# BT_HC05_v1.net
KiCad netlist of a schematic drawn in EAGLE
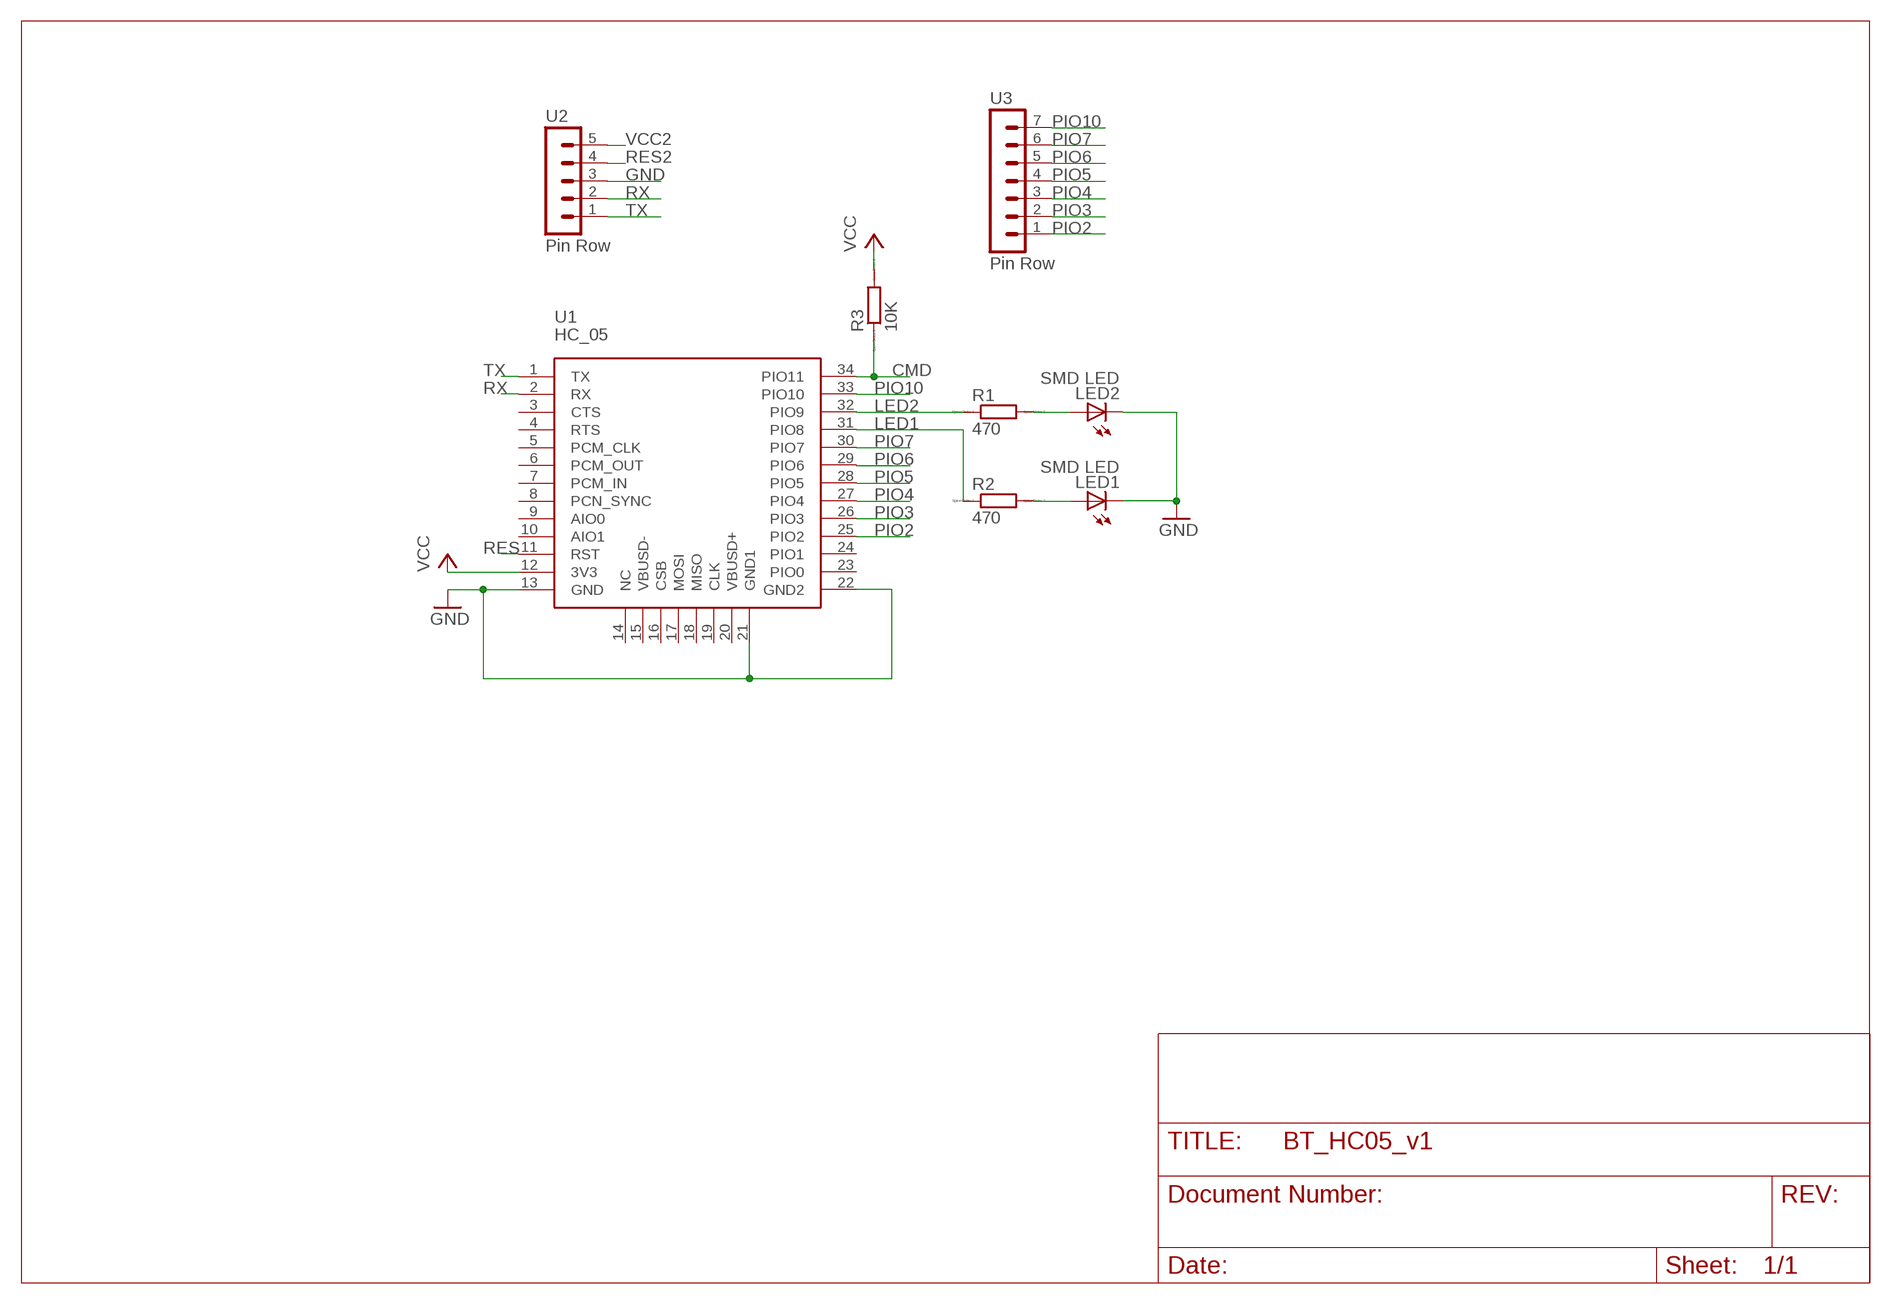
[diagram p0: schematic, sheet 1]

(export (version "E")
  (design (tool "Eeschema 10.0.6"))
  (components
    (comp (ref "LED1")
      (value "SMD LED")
      (footprint "eagle-import:CHIP-LED0805")
      (libsource (lib "eagle-import") (part "LEDCHIP-LED0805"))
    )
    (comp (ref "LED2")
      (value "SMD LED")
      (footprint "eagle-import:CHIP-LED0805")
      (libsource (lib "eagle-import") (part "LEDCHIP-LED0805"))
    )
    (comp (ref "R1")
      (value "470")
      (footprint "eagle-import:R0805")
      (libsource (lib "eagle-import") (part "R"))
    )
    (comp (ref "R2")
      (value "470")
      (footprint "eagle-import:R0805")
      (libsource (lib "eagle-import") (part "R"))
    )
    (comp (ref "R3")
      (value "10K")
      (footprint "eagle-import:R0805")
      (libsource (lib "eagle-import") (part "R"))
    )
    (comp (ref "U1")
      (value "HC_05")
      (footprint "eagle-import:BLUETOOTH_SMD")
      (libsource (lib "eagle-import") (part "HC_05"))
    )
    (comp (ref "U2")
      (value "Pin Row")
      (footprint "eagle-import:MAR05-1")
      (libsource (lib "eagle-import") (part "MAR05-1"))
    )
    (comp (ref "U3")
      (value "Pin Row")
      (footprint "eagle-import:MA07-1")
      (libsource (lib "eagle-import") (part "MA07-1"))
    )
  )
  (nets
    (net (code "1") (name "/CMD") (class "Default")
      (node (ref "R3") (pin "1") (pinfunction "1_1") (pintype "passive"))
      (node (ref "U1") (pin "34") (pinfunction "PIO11_34") (pintype "bidirectional"))
    )
    (net (code "2") (name "/LED1") (class "Default")
      (node (ref "R2") (pin "1") (pinfunction "1_1") (pintype "passive"))
      (node (ref "U1") (pin "31") (pinfunction "PIO8_31") (pintype "bidirectional"))
    )
    (net (code "3") (name "/LED2") (class "Default")
      (node (ref "R1") (pin "1") (pinfunction "1_1") (pintype "passive"))
      (node (ref "U1") (pin "32") (pinfunction "PIO9_32") (pintype "bidirectional"))
    )
    (net (code "4") (name "/PIO2") (class "Default")
      (node (ref "U1") (pin "25") (pinfunction "PIO2_25") (pintype "bidirectional"))
      (node (ref "U3") (pin "1") (pinfunction "1_1") (pintype "passive"))
    )
    (net (code "5") (name "/PIO3") (class "Default")
      (node (ref "U1") (pin "26") (pinfunction "PIO3_26") (pintype "bidirectional"))
      (node (ref "U3") (pin "2") (pinfunction "2_2") (pintype "passive"))
    )
    (net (code "6") (name "/PIO4") (class "Default")
      (node (ref "U1") (pin "27") (pinfunction "PIO4_27") (pintype "bidirectional"))
      (node (ref "U3") (pin "3") (pinfunction "3_3") (pintype "passive"))
    )
    (net (code "7") (name "/PIO5") (class "Default")
      (node (ref "U1") (pin "28") (pinfunction "PIO5_28") (pintype "bidirectional"))
      (node (ref "U3") (pin "4") (pinfunction "4_4") (pintype "passive"))
    )
    (net (code "8") (name "/PIO6") (class "Default")
      (node (ref "U1") (pin "29") (pinfunction "PIO6_29") (pintype "bidirectional"))
      (node (ref "U3") (pin "5") (pinfunction "5_5") (pintype "passive"))
    )
    (net (code "9") (name "/PIO7") (class "Default")
      (node (ref "U1") (pin "30") (pinfunction "PIO7_30") (pintype "bidirectional"))
      (node (ref "U3") (pin "6") (pinfunction "6_6") (pintype "passive"))
    )
    (net (code "10") (name "/PIO10") (class "Default")
      (node (ref "U1") (pin "33") (pinfunction "PIO10_33") (pintype "bidirectional"))
      (node (ref "U3") (pin "7") (pinfunction "7_7") (pintype "passive"))
    )
    (net (code "11") (name "/RES") (class "Default")
      (node (ref "U1") (pin "11") (pinfunction "RST_11") (pintype "bidirectional"))
    )
    (net (code "12") (name "/RES2") (class "Default")
      (node (ref "U2") (pin "4") (pinfunction "4_4") (pintype "passive"))
    )
    (net (code "13") (name "/RX") (class "Default")
      (node (ref "U1") (pin "2") (pinfunction "RX_2") (pintype "bidirectional"))
      (node (ref "U2") (pin "2") (pinfunction "2_2") (pintype "passive"))
    )
    (net (code "14") (name "/TX") (class "Default")
      (node (ref "U1") (pin "1") (pinfunction "TX_1") (pintype "bidirectional"))
      (node (ref "U2") (pin "1") (pinfunction "1_1") (pintype "passive"))
    )
    (net (code "15") (name "/VCC2") (class "Default")
      (node (ref "U2") (pin "5") (pinfunction "5_5") (pintype "passive"))
    )
    (net (code "16") (name "GND") (class "Default")
      (node (ref "LED1") (pin "C") (pinfunction "C_C") (pintype "passive"))
      (node (ref "LED2") (pin "C") (pinfunction "C_C") (pintype "passive"))
      (node (ref "U1") (pin "13") (pinfunction "GND_13") (pintype "bidirectional"))
      (node (ref "U1") (pin "21") (pinfunction "GND1_21") (pintype "bidirectional"))
      (node (ref "U1") (pin "22") (pinfunction "GND2_22") (pintype "bidirectional"))
      (node (ref "U2") (pin "3") (pinfunction "3_3") (pintype "passive"))
    )
    (net (code "17") (name "Net-(LED1-PadA)") (class "Default")
      (node (ref "LED1") (pin "A") (pinfunction "A_A") (pintype "passive"))
      (node (ref "R2") (pin "2") (pinfunction "2_2") (pintype "passive"))
    )
    (net (code "18") (name "Net-(LED2-PadA)") (class "Default")
      (node (ref "LED2") (pin "A") (pinfunction "A_A") (pintype "passive"))
      (node (ref "R1") (pin "2") (pinfunction "2_2") (pintype "passive"))
    )
    (net (code "19") (name "VCC") (class "Default")
      (node (ref "R3") (pin "2") (pinfunction "2_2") (pintype "passive"))
      (node (ref "U1") (pin "12") (pinfunction "3V3_12") (pintype "bidirectional"))
    )
    (net (code "20") (name "unconnected-(U1-AIO0-Pad9)") (class "Default")
      (node (ref "U1") (pin "9") (pinfunction "AIO0_9") (pintype "bidirectional"))
    )
    (net (code "21") (name "unconnected-(U1-AIO1-Pad10)") (class "Default")
      (node (ref "U1") (pin "10") (pinfunction "AIO1_10") (pintype "bidirectional"))
    )
    (net (code "22") (name "unconnected-(U1-CLK-Pad19)") (class "Default")
      (node (ref "U1") (pin "19") (pinfunction "CLK_19") (pintype "bidirectional"))
    )
    (net (code "23") (name "unconnected-(U1-CSB-Pad16)") (class "Default")
      (node (ref "U1") (pin "16") (pinfunction "CSB_16") (pintype "bidirectional"))
    )
    (net (code "24") (name "unconnected-(U1-CTS-Pad3)") (class "Default")
      (node (ref "U1") (pin "3") (pinfunction "CTS_3") (pintype "bidirectional"))
    )
    (net (code "25") (name "unconnected-(U1-MISO-Pad18)") (class "Default")
      (node (ref "U1") (pin "18") (pinfunction "MISO_18") (pintype "bidirectional"))
    )
    (net (code "26") (name "unconnected-(U1-MOSI-Pad17)") (class "Default")
      (node (ref "U1") (pin "17") (pinfunction "MOSI_17") (pintype "bidirectional"))
    )
    (net (code "27") (name "unconnected-(U1-NC-Pad14)") (class "Default")
      (node (ref "U1") (pin "14") (pinfunction "NC_14") (pintype "bidirectional"))
    )
    (net (code "28") (name "unconnected-(U1-PCM_CLK-Pad5)") (class "Default")
      (node (ref "U1") (pin "5") (pinfunction "PCM_CLK_5") (pintype "bidirectional"))
    )
    (net (code "29") (name "unconnected-(U1-PCM_IN-Pad7)") (class "Default")
      (node (ref "U1") (pin "7") (pinfunction "PCM_IN_7") (pintype "bidirectional"))
    )
    (net (code "30") (name "unconnected-(U1-PCM_OUT-Pad6)") (class "Default")
      (node (ref "U1") (pin "6") (pinfunction "PCM_OUT_6") (pintype "bidirectional"))
    )
    (net (code "31") (name "unconnected-(U1-PCN_SYNC-Pad8)") (class "Default")
      (node (ref "U1") (pin "8") (pinfunction "PCN_SYNC_8") (pintype "bidirectional"))
    )
    (net (code "32") (name "unconnected-(U1-PIO0-Pad23)") (class "Default")
      (node (ref "U1") (pin "23") (pinfunction "PIO0_23") (pintype "bidirectional"))
    )
    (net (code "33") (name "unconnected-(U1-PIO1-Pad24)") (class "Default")
      (node (ref "U1") (pin "24") (pinfunction "PIO1_24") (pintype "bidirectional"))
    )
    (net (code "34") (name "unconnected-(U1-RTS-Pad4)") (class "Default")
      (node (ref "U1") (pin "4") (pinfunction "RTS_4") (pintype "bidirectional"))
    )
    (net (code "35") (name "unconnected-(U1-VBUSD+-Pad20)") (class "Default")
      (node (ref "U1") (pin "20") (pinfunction "VBUSD+_20") (pintype "bidirectional"))
    )
    (net (code "36") (name "unconnected-(U1-VBUSD--Pad15)") (class "Default")
      (node (ref "U1") (pin "15") (pinfunction "VBUSD-_15") (pintype "bidirectional"))
    )
  )
)
